# pic32.net
KiCad netlist of a schematic drawn in EAGLE
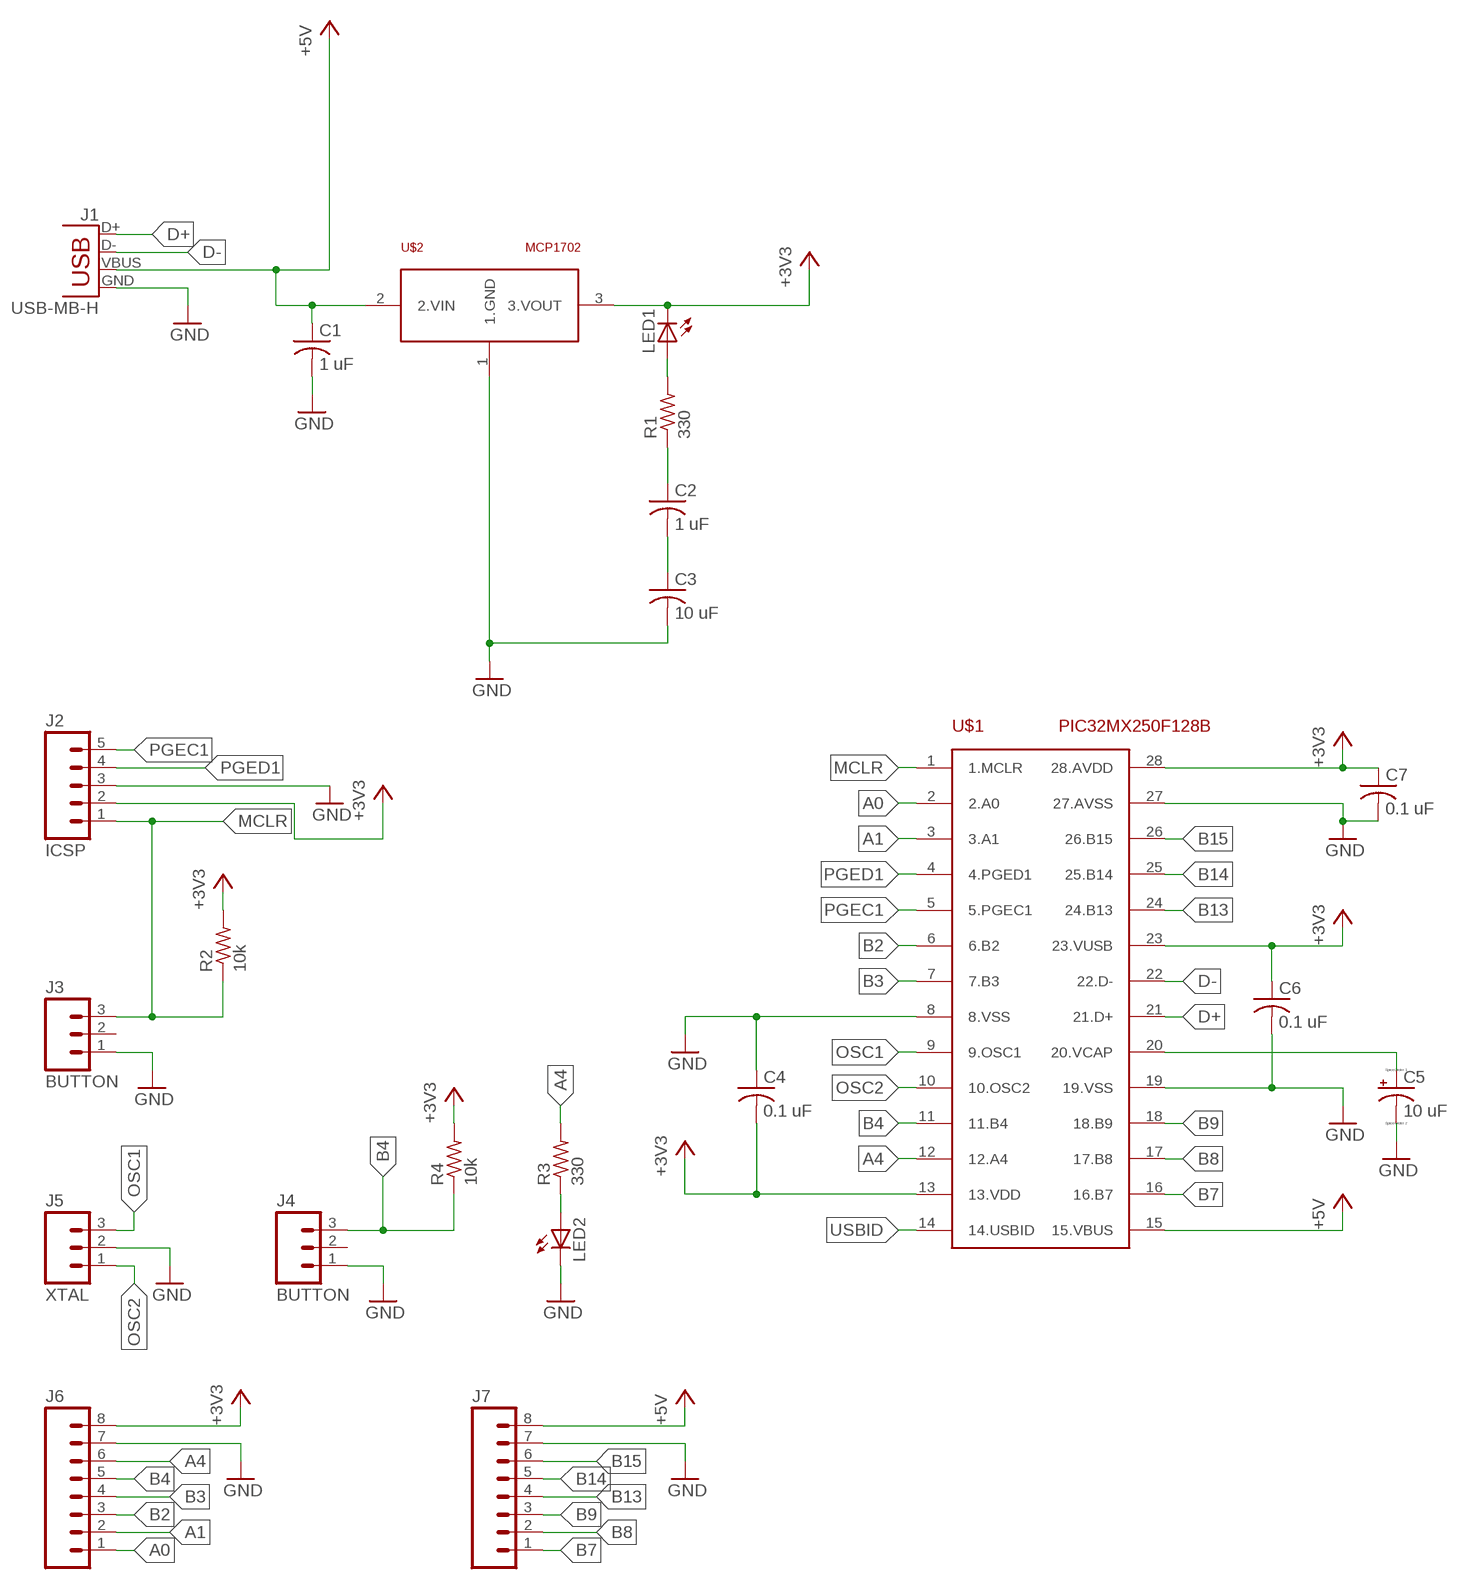
[diagram p0: schematic, sheet 1]

(export (version "E")
  (design (tool "Eeschema 10.0.6"))
  (components
    (comp (ref "C1")
      (value "1 uF")
      (footprint "eagle-import:C025-024X044")
      (libsource (lib "eagle-import") (part "C-US025-024X044"))
    )
    (comp (ref "C2")
      (value "1 uF")
      (footprint "eagle-import:C025-024X044")
      (libsource (lib "eagle-import") (part "C-US025-024X044"))
    )
    (comp (ref "C3")
      (value "10 uF")
      (footprint "eagle-import:C025-024X044")
      (libsource (lib "eagle-import") (part "C-US025-024X044"))
    )
    (comp (ref "C4")
      (value "0.1 uF")
      (footprint "eagle-import:C025-024X044")
      (libsource (lib "eagle-import") (part "C-US025-024X044"))
    )
    (comp (ref "C5")
      (value "10 uF")
      (footprint "eagle-import:E1,8-4")
      (libsource (lib "eagle-import") (part "CPOL-USE1.8-4"))
    )
    (comp (ref "C6")
      (value "0.1 uF")
      (footprint "eagle-import:C025-024X044")
      (libsource (lib "eagle-import") (part "C-US025-024X044"))
    )
    (comp (ref "C7")
      (value "0.1 uF")
      (footprint "eagle-import:C025-024X044")
      (libsource (lib "eagle-import") (part "C-US025-024X044"))
    )
    (comp (ref "J1")
      (value "USB-MB-H")
      (footprint "eagle-import:USB-MB-H")
      (libsource (lib "eagle-import") (part "USB-MB-H"))
    )
    (comp (ref "J2")
      (value "ICSP")
      (footprint "eagle-import:1X05")
      (libsource (lib "eagle-import") (part "M05PTH"))
    )
    (comp (ref "J3")
      (value "BUTTON")
      (footprint "eagle-import:1X03")
      (libsource (lib "eagle-import") (part "M03PTH"))
    )
    (comp (ref "J4")
      (value "BUTTON")
      (footprint "eagle-import:1X03")
      (libsource (lib "eagle-import") (part "M03PTH"))
    )
    (comp (ref "J5")
      (value "XTAL")
      (footprint "eagle-import:1X03")
      (libsource (lib "eagle-import") (part "M03PTH"))
    )
    (comp (ref "J6")
      (value "M08")
      (footprint "eagle-import:1X08_ROUND")
      (libsource (lib "eagle-import") (part "M08"))
    )
    (comp (ref "J7")
      (value "M08")
      (footprint "eagle-import:1X08_ROUND")
      (libsource (lib "eagle-import") (part "M08"))
    )
    (comp (ref "LED1")
      (value "LED3MM")
      (footprint "eagle-import:LED3MM")
      (libsource (lib "eagle-import") (part "LED3MM"))
    )
    (comp (ref "LED2")
      (value "LED3MM")
      (footprint "eagle-import:LED3MM")
      (libsource (lib "eagle-import") (part "LED3MM"))
    )
    (comp (ref "R1")
      (value "330")
      (footprint "eagle-import:0207_10")
      (libsource (lib "eagle-import") (part "R-US_0207/10"))
    )
    (comp (ref "R2")
      (value "10k")
      (footprint "eagle-import:0207_10")
      (libsource (lib "eagle-import") (part "R-US_0207/10"))
    )
    (comp (ref "R3")
      (value "330")
      (footprint "eagle-import:0207_10")
      (libsource (lib "eagle-import") (part "R-US_0207/10"))
    )
    (comp (ref "R4")
      (value "10k")
      (footprint "eagle-import:0207_10")
      (libsource (lib "eagle-import") (part "R-US_0207/10"))
    )
    (comp (ref "U$1")
      (value "PIC32MX250F128B")
      (footprint "eagle-import:DIL28-3")
      (libsource (lib "eagle-import") (part "PIC32MX250F128B"))
    )
    (comp (ref "U$2")
      (value "MCP1702")
      (footprint "eagle-import:TO92")
      (libsource (lib "eagle-import") (part "MCP1702"))
    )
  )
  (nets
    (net (code "1") (name "+3V3") (class "Default")
      (node (ref "C4") (pin "2") (pinfunction "2_2") (pintype "passive"))
      (node (ref "C6") (pin "1") (pinfunction "1_1") (pintype "passive"))
      (node (ref "C7") (pin "1") (pinfunction "1_1") (pintype "passive"))
      (node (ref "J2") (pin "2") (pinfunction "2_2") (pintype "passive"))
      (node (ref "J6") (pin "8") (pinfunction "8_8") (pintype "passive"))
      (node (ref "LED1") (pin "K") (pinfunction "C_K") (pintype "passive"))
      (node (ref "R2") (pin "2") (pinfunction "2_2") (pintype "passive"))
      (node (ref "R4") (pin "2") (pinfunction "2_2") (pintype "passive"))
      (node (ref "U$1") (pin "13") (pinfunction "13.VDD_13") (pintype "bidirectional"))
      (node (ref "U$1") (pin "23") (pinfunction "23.VUSB_23") (pintype "bidirectional"))
      (node (ref "U$1") (pin "28") (pinfunction "28.AVDD_28") (pintype "bidirectional"))
      (node (ref "U$2") (pin "3") (pinfunction "3.VOUT_3") (pintype "bidirectional"))
    )
    (net (code "2") (name "+5V") (class "Default")
      (node (ref "C1") (pin "1") (pinfunction "1_1") (pintype "passive"))
      (node (ref "J1") (pin "VBUS") (pinfunction "VBUS_VBUS") (pintype "bidirectional"))
      (node (ref "J7") (pin "8") (pinfunction "8_8") (pintype "passive"))
      (node (ref "U$1") (pin "15") (pinfunction "15.VBUS_15") (pintype "bidirectional"))
      (node (ref "U$2") (pin "2") (pinfunction "2.VIN_2") (pintype "bidirectional"))
    )
    (net (code "3") (name "A0") (class "Default")
      (node (ref "J6") (pin "1") (pinfunction "1_1") (pintype "passive"))
      (node (ref "U$1") (pin "2") (pinfunction "2.A0_2") (pintype "bidirectional"))
    )
    (net (code "4") (name "A1") (class "Default")
      (node (ref "J6") (pin "2") (pinfunction "2_2") (pintype "passive"))
      (node (ref "U$1") (pin "3") (pinfunction "3.A1_3") (pintype "bidirectional"))
    )
    (net (code "5") (name "A4") (class "Default")
      (node (ref "J6") (pin "6") (pinfunction "6_6") (pintype "passive"))
      (node (ref "R3") (pin "2") (pinfunction "2_2") (pintype "passive"))
      (node (ref "U$1") (pin "12") (pinfunction "12.A4_12") (pintype "bidirectional"))
    )
    (net (code "6") (name "B2") (class "Default")
      (node (ref "J6") (pin "3") (pinfunction "3_3") (pintype "passive"))
      (node (ref "U$1") (pin "6") (pinfunction "6.B2_6") (pintype "bidirectional"))
    )
    (net (code "7") (name "B3") (class "Default")
      (node (ref "J6") (pin "4") (pinfunction "4_4") (pintype "passive"))
      (node (ref "U$1") (pin "7") (pinfunction "7.B3_7") (pintype "bidirectional"))
    )
    (net (code "8") (name "B4") (class "Default")
      (node (ref "J4") (pin "3") (pinfunction "3_3") (pintype "passive"))
      (node (ref "J6") (pin "5") (pinfunction "5_5") (pintype "passive"))
      (node (ref "R4") (pin "1") (pinfunction "1_1") (pintype "passive"))
      (node (ref "U$1") (pin "11") (pinfunction "11.B4_11") (pintype "bidirectional"))
    )
    (net (code "9") (name "B7") (class "Default")
      (node (ref "J7") (pin "1") (pinfunction "1_1") (pintype "passive"))
      (node (ref "U$1") (pin "16") (pinfunction "16.B7_16") (pintype "bidirectional"))
    )
    (net (code "10") (name "B8") (class "Default")
      (node (ref "J7") (pin "2") (pinfunction "2_2") (pintype "passive"))
      (node (ref "U$1") (pin "17") (pinfunction "17.B8_17") (pintype "bidirectional"))
    )
    (net (code "11") (name "B9") (class "Default")
      (node (ref "J7") (pin "3") (pinfunction "3_3") (pintype "passive"))
      (node (ref "U$1") (pin "18") (pinfunction "18.B9_18") (pintype "bidirectional"))
    )
    (net (code "12") (name "B13") (class "Default")
      (node (ref "J7") (pin "4") (pinfunction "4_4") (pintype "passive"))
      (node (ref "U$1") (pin "24") (pinfunction "24.B13_24") (pintype "bidirectional"))
    )
    (net (code "13") (name "B14") (class "Default")
      (node (ref "J7") (pin "5") (pinfunction "5_5") (pintype "passive"))
      (node (ref "U$1") (pin "25") (pinfunction "25.B14_25") (pintype "bidirectional"))
    )
    (net (code "14") (name "B15") (class "Default")
      (node (ref "J7") (pin "6") (pinfunction "6_6") (pintype "passive"))
      (node (ref "U$1") (pin "26") (pinfunction "26.B15_26") (pintype "bidirectional"))
    )
    (net (code "15") (name "D+") (class "Default")
      (node (ref "J1") (pin "D+") (pinfunction "D+_D+") (pintype "bidirectional"))
      (node (ref "U$1") (pin "21") (pinfunction "21.D+_21") (pintype "bidirectional"))
    )
    (net (code "16") (name "D-") (class "Default")
      (node (ref "J1") (pin "D-") (pinfunction "D-_D-") (pintype "bidirectional"))
      (node (ref "U$1") (pin "22") (pinfunction "22.D-_22") (pintype "bidirectional"))
    )
    (net (code "17") (name "GND") (class "Default")
      (node (ref "C1") (pin "2") (pinfunction "2_2") (pintype "passive"))
      (node (ref "C3") (pin "2") (pinfunction "2_2") (pintype "passive"))
      (node (ref "C4") (pin "1") (pinfunction "1_1") (pintype "passive"))
      (node (ref "C5") (pin "-") (pinfunction "-_-") (pintype "passive"))
      (node (ref "C6") (pin "2") (pinfunction "2_2") (pintype "passive"))
      (node (ref "C7") (pin "2") (pinfunction "2_2") (pintype "passive"))
      (node (ref "J1") (pin "GND") (pinfunction "GND_GND") (pintype "bidirectional"))
      (node (ref "J2") (pin "3") (pinfunction "3_3") (pintype "passive"))
      (node (ref "J3") (pin "1") (pinfunction "1_1") (pintype "passive"))
      (node (ref "J4") (pin "1") (pinfunction "1_1") (pintype "passive"))
      (node (ref "J5") (pin "2") (pinfunction "2_2") (pintype "passive"))
      (node (ref "J6") (pin "7") (pinfunction "7_7") (pintype "passive"))
      (node (ref "J7") (pin "7") (pinfunction "7_7") (pintype "passive"))
      (node (ref "LED2") (pin "K") (pinfunction "C_K") (pintype "passive"))
      (node (ref "U$1") (pin "19") (pinfunction "19.VSS_19") (pintype "bidirectional"))
      (node (ref "U$1") (pin "27") (pinfunction "27.AVSS_27") (pintype "bidirectional"))
      (node (ref "U$1") (pin "8") (pinfunction "8.VSS_8") (pintype "bidirectional"))
      (node (ref "U$2") (pin "1") (pinfunction "1.GND_1") (pintype "bidirectional"))
    )
    (net (code "18") (name "MCLR") (class "Default")
      (node (ref "J2") (pin "1") (pinfunction "1_1") (pintype "passive"))
      (node (ref "J3") (pin "3") (pinfunction "3_3") (pintype "passive"))
      (node (ref "R2") (pin "1") (pinfunction "1_1") (pintype "passive"))
      (node (ref "U$1") (pin "1") (pinfunction "1.MCLR_1") (pintype "bidirectional"))
    )
    (net (code "19") (name "Net-(C2-Pad1)") (class "Default")
      (node (ref "C2") (pin "1") (pinfunction "1_1") (pintype "passive"))
      (node (ref "R1") (pin "1") (pinfunction "1_1") (pintype "passive"))
    )
    (net (code "20") (name "Net-(C2-Pad2)") (class "Default")
      (node (ref "C2") (pin "2") (pinfunction "2_2") (pintype "passive"))
      (node (ref "C3") (pin "1") (pinfunction "1_1") (pintype "passive"))
    )
    (net (code "21") (name "Net-(LED1-PadA)") (class "Default")
      (node (ref "LED1") (pin "A") (pinfunction "A_A") (pintype "passive"))
      (node (ref "R1") (pin "2") (pinfunction "2_2") (pintype "passive"))
    )
    (net (code "22") (name "Net-(LED2-PadA)") (class "Default")
      (node (ref "LED2") (pin "A") (pinfunction "A_A") (pintype "passive"))
      (node (ref "R3") (pin "1") (pinfunction "1_1") (pintype "passive"))
    )
    (net (code "23") (name "Net-(U$1-20.VCAP)") (class "Default")
      (node (ref "C5") (pin "+") (pinfunction "+_+") (pintype "passive"))
      (node (ref "U$1") (pin "20") (pinfunction "20.VCAP_20") (pintype "bidirectional"))
    )
    (net (code "24") (name "OSC1") (class "Default")
      (node (ref "J5") (pin "3") (pinfunction "3_3") (pintype "passive"))
      (node (ref "U$1") (pin "9") (pinfunction "9.OSC1_9") (pintype "bidirectional"))
    )
    (net (code "25") (name "OSC2") (class "Default")
      (node (ref "J5") (pin "1") (pinfunction "1_1") (pintype "passive"))
      (node (ref "U$1") (pin "10") (pinfunction "10.OSC2_10") (pintype "bidirectional"))
    )
    (net (code "26") (name "PGEC1") (class "Default")
      (node (ref "J2") (pin "5") (pinfunction "5_5") (pintype "passive"))
      (node (ref "U$1") (pin "5") (pinfunction "5.PGEC1_5") (pintype "bidirectional"))
    )
    (net (code "27") (name "PGED1") (class "Default")
      (node (ref "J2") (pin "4") (pinfunction "4_4") (pintype "passive"))
      (node (ref "U$1") (pin "4") (pinfunction "4.PGED1_4") (pintype "bidirectional"))
    )
    (net (code "28") (name "USBID") (class "Default")
      (node (ref "U$1") (pin "14") (pinfunction "14.USBID_14") (pintype "bidirectional"))
    )
    (net (code "29") (name "unconnected-(J3-Pad2)") (class "Default")
      (node (ref "J3") (pin "2") (pinfunction "2_2") (pintype "passive"))
    )
    (net (code "30") (name "unconnected-(J4-Pad2)") (class "Default")
      (node (ref "J4") (pin "2") (pinfunction "2_2") (pintype "passive"))
    )
  )
)
